# 20240913.net
KiCad netlist of a schematic drawn in Altium Designer
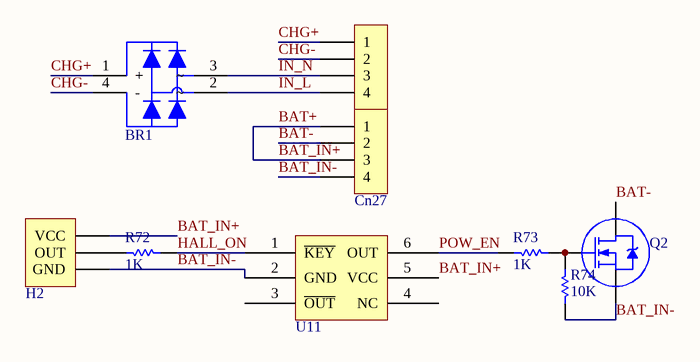
[diagram p0: 磁開關電路_20240913.SchDoc]

(export (version "E")
  (design (tool "Eeschema 10.0.6"))
  (components
    (comp (ref "BR1")
      (value "KBL005")
      (footprint "BridgeRectifier_KBL005E451")
      (description "橋式整流")
      (libsource (lib "MyLibray") (part "BridgeRectifier"))
    )
    (comp (ref "Cn22")
      (value "KF2510-4")
      (footprint "Connector_KF2510-4W")
      (description "接線端子")
      (libsource (lib "MyLibray") (part "Contact(4P)"))
    )
    (comp (ref "Cn27")
      (value "KF2510-4")
      (footprint "Connector_KF2510-4W")
      (description "接線端子")
      (libsource (lib "MyLibray") (part "Contact(4P)"))
    )
    (comp (ref "H2")
      (value "A3212")
      (footprint "SOT 23-3")
      (description "感測器_霍爾")
      (libsource (lib "MyLibray") (part "Sensor_Hall"))
    )
    (comp (ref "Q2")
      (value "TIP122")
      (footprint "TO-220 1>3>2")
      (description "場效電晶體_N")
      (libsource (lib "MyLibray") (part "MOS-N"))
    )
    (comp (ref "R72")
      (value "1K")
      (footprint "Res_1/4")
      (description "電阻")
      (libsource (lib "MyLibray") (part "Res"))
    )
    (comp (ref "R73")
      (value "1K")
      (footprint "Res_1/4")
      (description "電阻")
      (libsource (lib "MyLibray") (part "Res"))
    )
    (comp (ref "R74")
      (value "10K")
      (footprint "Res_1/4")
      (description "電阻")
      (libsource (lib "MyLibray") (part "Res"))
    )
    (comp (ref "U11")
      (value "CS2130")
      (footprint "SOT 23-6")
      (description "單鍵ON/OFF芯片")
      (libsource (lib "MyLibray") (part "CS2130"))
    )
  )
  (nets
    (net (code "1") (name "/BAT+") (class "Default")
      (node (ref "Cn27") (pin "1") (pinfunction "1_1") (pintype "passive"))
      (node (ref "Cn27") (pin "3") (pinfunction "3_3") (pintype "passive"))
      (node (ref "H2") (pin "1") (pinfunction "VCC_1") (pintype "power_in"))
      (node (ref "U11") (pin "5") (pinfunction "VCC_5") (pintype "passive"))
    )
    (net (code "2") (name "/BAT-") (class "Default")
      (node (ref "Cn27") (pin "2") (pinfunction "2_2") (pintype "passive"))
      (node (ref "Q2") (pin "3") (pinfunction "D_3") (pintype "passive"))
    )
    (net (code "3") (name "/BAT_IN-") (class "Default")
      (node (ref "Cn27") (pin "4") (pinfunction "4_4") (pintype "passive"))
      (node (ref "H2") (pin "3") (pinfunction "GND_3") (pintype "power_in"))
      (node (ref "Q2") (pin "2") (pinfunction "S_2") (pintype "passive"))
      (node (ref "R74") (pin "2") (pinfunction "2_2") (pintype "passive"))
      (node (ref "U11") (pin "2") (pinfunction "GND_2") (pintype "passive"))
    )
    (net (code "4") (name "/CHG+") (class "Default")
      (node (ref "BR1") (pin "1") (pinfunction "+_1") (pintype "passive"))
      (node (ref "Cn22") (pin "1") (pinfunction "1_1") (pintype "passive"))
    )
    (net (code "5") (name "/CHG-") (class "Default")
      (node (ref "BR1") (pin "4") (pinfunction "-_4") (pintype "passive"))
      (node (ref "Cn22") (pin "2") (pinfunction "2_2") (pintype "passive"))
    )
    (net (code "6") (name "/HALL_ON") (class "Default")
      (node (ref "R72") (pin "1") (pinfunction "1_1") (pintype "passive"))
      (node (ref "U11") (pin "1") (pinfunction "~{KEY}_1") (pintype "passive"))
    )
    (net (code "7") (name "/IN_L") (class "Default")
      (node (ref "BR1") (pin "2") (pinfunction "~_2") (pintype "passive"))
      (node (ref "Cn22") (pin "4") (pinfunction "4_4") (pintype "passive"))
    )
    (net (code "8") (name "/IN_N") (class "Default")
      (node (ref "BR1") (pin "3") (pinfunction "~_3") (pintype "passive"))
      (node (ref "Cn22") (pin "3") (pinfunction "3_3") (pintype "passive"))
    )
    (net (code "9") (name "/POW_EN") (class "Default")
      (node (ref "R73") (pin "2") (pinfunction "2_2") (pintype "passive"))
      (node (ref "U11") (pin "6") (pinfunction "OUT_6") (pintype "passive"))
    )
    (net (code "10") (name "Net-(H2-OUT)") (class "Default")
      (node (ref "H2") (pin "2") (pinfunction "OUT_2") (pintype "power_in"))
      (node (ref "R72") (pin "2") (pinfunction "2_2") (pintype "passive"))
    )
    (net (code "11") (name "Net-(Q2-G)") (class "Default")
      (node (ref "Q2") (pin "1") (pinfunction "G_1") (pintype "passive"))
      (node (ref "R73") (pin "1") (pinfunction "1_1") (pintype "passive"))
      (node (ref "R74") (pin "1") (pinfunction "1_1") (pintype "passive"))
    )
    (net (code "12") (name "unconnected-(U11-NC-Pad4)") (class "Default")
      (node (ref "U11") (pin "4") (pinfunction "NC_4") (pintype "passive"))
    )
    (net (code "13") (name "unconnected-(U11-~{OUT}-Pad3)") (class "Default")
      (node (ref "U11") (pin "3") (pinfunction "~{OUT}_3") (pintype "passive"))
    )
  )
)
